# LORA.net
KiCad netlist of a schematic drawn in Altium Designer
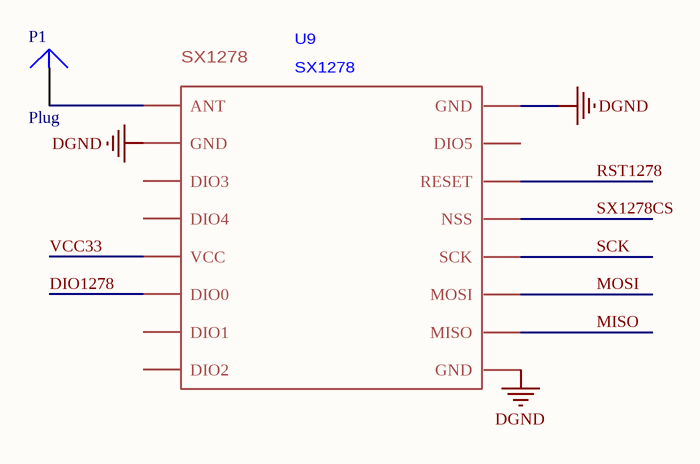
[diagram p0: LORA.SchDoc]

(export (version "E")
  (design (tool "Eeschema 10.0.6"))
  (components
    (comp (ref "P1")
      (value "Plug")
      (footprint "PIN1")
      (fields (field (name "PUBLISHER") "Altium Limited"))
      (libsource (lib "Miscellaneous Connectors") (part "Plug"))
    )
    (comp (ref "U9")
      (value "SX1278")
      (footprint "SX1278_2")
      (description "lora模块")
      (libsource (lib "altium-import") (part "root_0_SX1278_2_"))
    )
  )
  (nets
    (net (code "1") (name "/DIO1278") (class "Default")
      (node (ref "U9") (pin "DIO0") (pinfunction "DIO0_DIO0") (pintype "passive"))
    )
    (net (code "2") (name "/MISO") (class "Default")
      (node (ref "U9") (pin "MISO") (pinfunction "MISO_MISO") (pintype "passive"))
    )
    (net (code "3") (name "/MOSI") (class "Default")
      (node (ref "U9") (pin "MOSI") (pinfunction "MOSI_MOSI") (pintype "passive"))
    )
    (net (code "4") (name "/RST1278") (class "Default")
      (node (ref "U9") (pin "RESET") (pinfunction "RESET_RESET") (pintype "passive"))
    )
    (net (code "5") (name "/SCK") (class "Default")
      (node (ref "U9") (pin "SCK") (pinfunction "SCK_SCK") (pintype "passive"))
    )
    (net (code "6") (name "/SX1278CS") (class "Default")
      (node (ref "U9") (pin "NSS") (pinfunction "NSS_NSS") (pintype "passive"))
    )
    (net (code "7") (name "/VCC33") (class "Default")
      (node (ref "U9") (pin "VCC") (pinfunction "VCC_VCC") (pintype "passive"))
    )
    (net (code "8") (name "DGND") (class "Default")
      (node (ref "U9") (pin "GND@1") (pinfunction "GND_GND@1") (pintype "passive"))
      (node (ref "U9") (pin "GND@2") (pinfunction "GND_GND@2") (pintype "passive"))
      (node (ref "U9") (pin "GND@3") (pinfunction "GND_GND@3") (pintype "passive"))
    )
    (net (code "9") (name "Net-(P1-Pad1)") (class "Default")
      (node (ref "P1") (pin "1") (pinfunction "1_1") (pintype "passive"))
      (node (ref "U9") (pin "ANT") (pinfunction "ANT_ANT") (pintype "passive"))
    )
    (net (code "10") (name "unconnected-(U9-PadDIO1)") (class "Default")
      (node (ref "U9") (pin "DIO1") (pinfunction "DIO1_DIO1") (pintype "passive"))
    )
    (net (code "11") (name "unconnected-(U9-PadDIO2)") (class "Default")
      (node (ref "U9") (pin "DIO2") (pinfunction "DIO2_DIO2") (pintype "passive"))
    )
    (net (code "12") (name "unconnected-(U9-PadDIO3)") (class "Default")
      (node (ref "U9") (pin "DIO3") (pinfunction "DIO3_DIO3") (pintype "passive"))
    )
    (net (code "13") (name "unconnected-(U9-PadDIO4)") (class "Default")
      (node (ref "U9") (pin "DIO4") (pinfunction "DIO4_DIO4") (pintype "passive"))
    )
    (net (code "14") (name "unconnected-(U9-PadDIO5)") (class "Default")
      (node (ref "U9") (pin "DIO5") (pinfunction "DIO5_DIO5") (pintype "passive"))
    )
  )
)
